# withAnalog.net
KiCad netlist of a schematic drawn in EAGLE
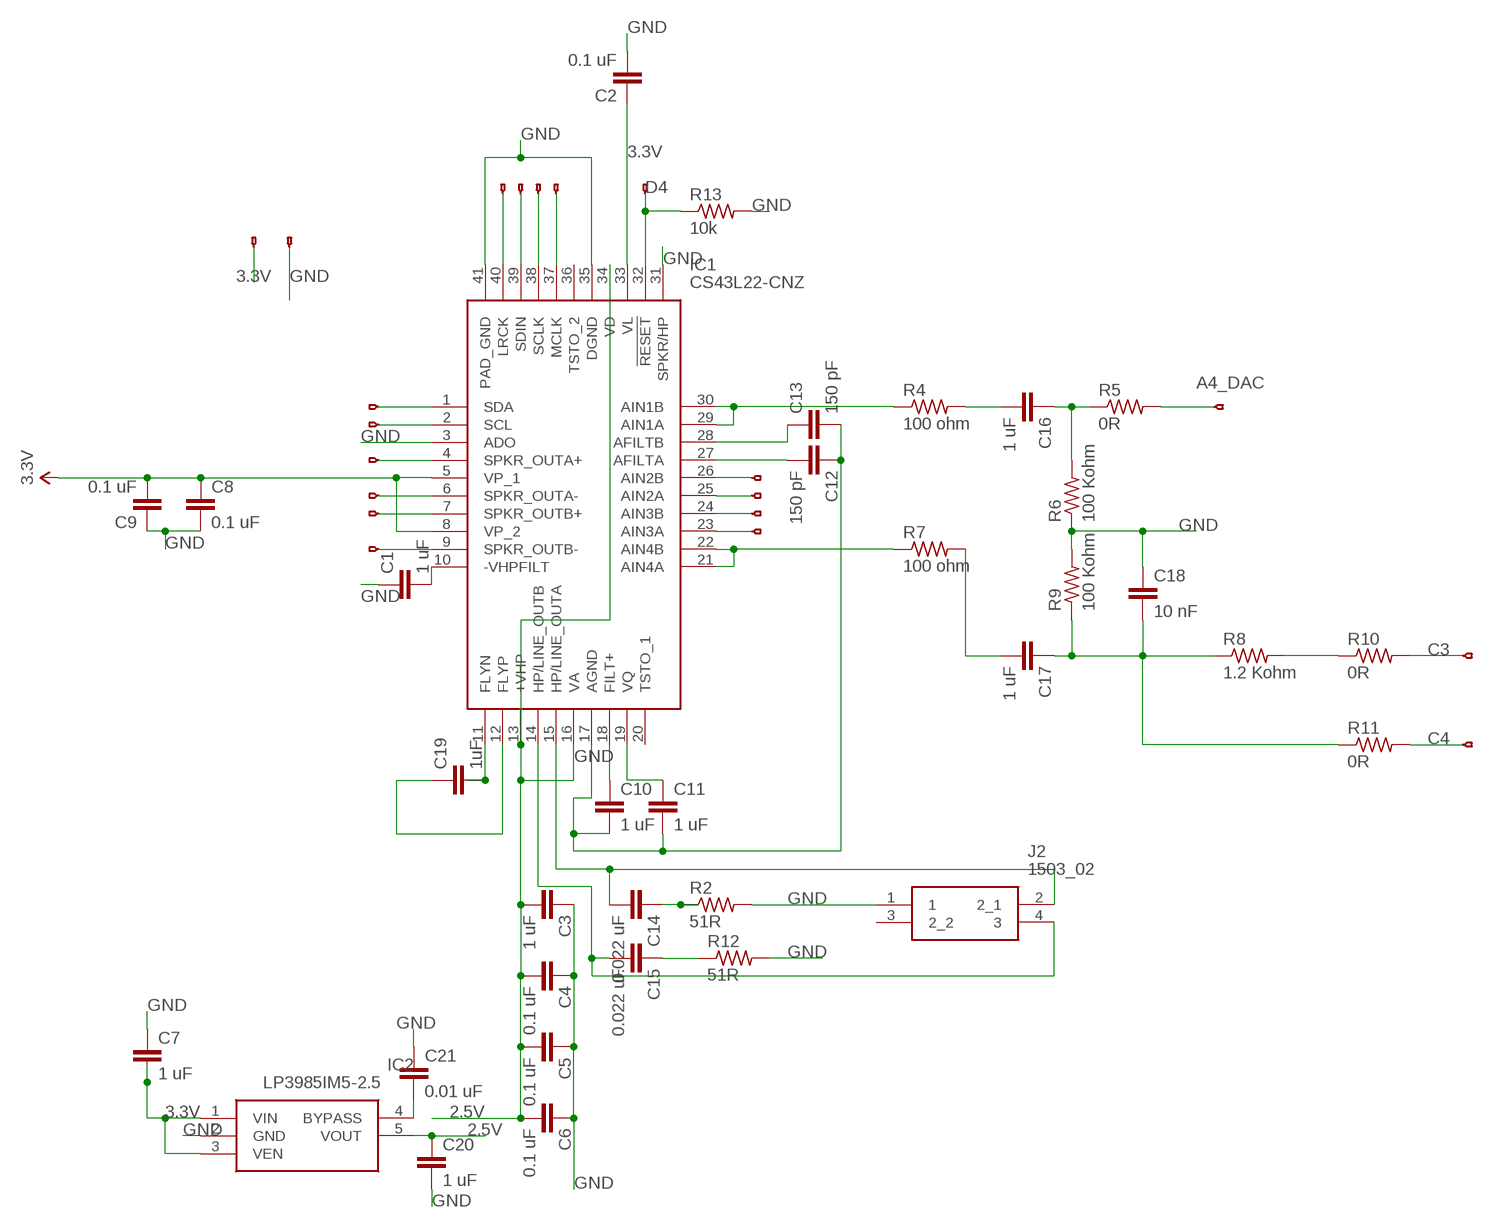
[diagram p0: schematic, sheet 1]

(export (version "E")
  (design (tool "Eeschema 10.0.6"))
  (components
    (comp (ref "C1")
      (value "1 uF")
      (footprint "eagle-import:CAP-PTH-SMALL-KIT")
      (libsource (lib "eagle-import") (part "CAPKIT"))
    )
    (comp (ref "C2")
      (value "0.1 uF")
      (footprint "eagle-import:CAP-PTH-SMALL-KIT")
      (libsource (lib "eagle-import") (part "CAPKIT"))
    )
    (comp (ref "C3")
      (value "1 uF")
      (footprint "eagle-import:CAP-PTH-SMALL-KIT")
      (libsource (lib "eagle-import") (part "CAPKIT"))
    )
    (comp (ref "C4")
      (value "0.1 uF")
      (footprint "eagle-import:CAP-PTH-SMALL-KIT")
      (libsource (lib "eagle-import") (part "CAPKIT"))
    )
    (comp (ref "C5")
      (value "0.1 uF")
      (footprint "eagle-import:CAP-PTH-SMALL-KIT")
      (libsource (lib "eagle-import") (part "CAPKIT"))
    )
    (comp (ref "C6")
      (value "0.1 uF")
      (footprint "eagle-import:CAP-PTH-SMALL-KIT")
      (libsource (lib "eagle-import") (part "CAPKIT"))
    )
    (comp (ref "C7")
      (value "1 uF")
      (footprint "eagle-import:CAP-PTH-SMALL-KIT")
      (libsource (lib "eagle-import") (part "CAPKIT"))
    )
    (comp (ref "C8")
      (value "0.1 uF")
      (footprint "eagle-import:CAP-PTH-SMALL-KIT")
      (libsource (lib "eagle-import") (part "CAPKIT"))
    )
    (comp (ref "C9")
      (value "0.1 uF")
      (footprint "eagle-import:CAP-PTH-SMALL-KIT")
      (libsource (lib "eagle-import") (part "CAPKIT"))
    )
    (comp (ref "C10")
      (value "1 uF")
      (footprint "eagle-import:CAP-PTH-SMALL-KIT")
      (libsource (lib "eagle-import") (part "CAPKIT"))
    )
    (comp (ref "C11")
      (value "1 uF")
      (footprint "eagle-import:CAP-PTH-SMALL-KIT")
      (libsource (lib "eagle-import") (part "CAPKIT"))
    )
    (comp (ref "C12")
      (value "150 pF")
      (footprint "eagle-import:CAP-PTH-SMALL-KIT")
      (libsource (lib "eagle-import") (part "CAPKIT"))
    )
    (comp (ref "C13")
      (value "150 pF")
      (footprint "eagle-import:CAP-PTH-SMALL-KIT")
      (libsource (lib "eagle-import") (part "CAPKIT"))
    )
    (comp (ref "C14")
      (value "0.022 uF")
      (footprint "eagle-import:CAP-PTH-SMALL-KIT")
      (libsource (lib "eagle-import") (part "CAPKIT"))
    )
    (comp (ref "C15")
      (value "0.022 uF")
      (footprint "eagle-import:CAP-PTH-SMALL-KIT")
      (libsource (lib "eagle-import") (part "CAPKIT"))
    )
    (comp (ref "C16")
      (value "1 uF")
      (footprint "eagle-import:CAP-PTH-SMALL-KIT")
      (libsource (lib "eagle-import") (part "CAPKIT"))
    )
    (comp (ref "C17")
      (value "1 uF")
      (footprint "eagle-import:CAP-PTH-SMALL-KIT")
      (libsource (lib "eagle-import") (part "CAPKIT"))
    )
    (comp (ref "C18")
      (value "10 nF")
      (footprint "eagle-import:CAP-PTH-SMALL-KIT")
      (libsource (lib "eagle-import") (part "CAPKIT"))
    )
    (comp (ref "C19")
      (value "1uF")
      (footprint "eagle-import:C2.5-3")
      (libsource (lib "eagle-import") (part "C2,5-3"))
    )
    (comp (ref "C20")
      (value "1 uF")
      (footprint "eagle-import:CAP-PTH-SMALL-KIT")
      (libsource (lib "eagle-import") (part "CAPKIT"))
    )
    (comp (ref "C21")
      (value "0.01 uF")
      (footprint "eagle-import:CAP-PTH-SMALL-KIT")
      (libsource (lib "eagle-import") (part "CAPKIT"))
    )
    (comp (ref "IC1")
      (value "CS43L22-CNZ")
      (footprint "eagle-import:QFN50P600X600X100-41N")
      (fields
        (field (name "MOUSER_PART_NUMBER") "777-CS43L22-CNZ")
        (field (name "RS_PART_NUMBER") "7165851P")
      )
      (libsource (lib "eagle-import") (part "CS43L22-CNZ"))
    )
    (comp (ref "IC2")
      (value "LP3985IM5-2.5")
      (footprint "eagle-import:SOT95P300X120-5N")
      (fields
        (field (name "MOUSER_PART_NUMBER") "926-LP3985IM5-25")
        (field (name "RS_PART_NUMBER") "4433167")
      )
      (libsource (lib "eagle-import") (part "LP3985IM5-2.5"))
    )
    (comp (ref "J2")
      (value "1503_02")
      (footprint "eagle-import:150302")
      (fields (field (name "MANUFACTURER_PART_NUMBER") "1503 02"))
      (libsource (lib "eagle-import") (part "1503_02"))
    )
    (comp (ref "JP1")
      (value "HEADERHOLE-HEADERHOLE")
      (footprint "eagle-import:1X1-HEADER-HOLE")
      (libsource (lib "eagle-import") (part "HEADERHOLE-HEADERHOLE"))
    )
    (comp (ref "JP2")
      (value "HEADERHOLE-HEADERHOLE")
      (footprint "eagle-import:1X1-HEADER-HOLE")
      (libsource (lib "eagle-import") (part "HEADERHOLE-HEADERHOLE"))
    )
    (comp (ref "JP3")
      (value "HEADERHOLE-HEADERHOLE")
      (footprint "eagle-import:1X1-HEADER-HOLE")
      (libsource (lib "eagle-import") (part "HEADERHOLE-HEADERHOLE"))
    )
    (comp (ref "JP4")
      (value "HEADERHOLE-HEADERHOLE")
      (footprint "eagle-import:1X1-HEADER-HOLE")
      (libsource (lib "eagle-import") (part "HEADERHOLE-HEADERHOLE"))
    )
    (comp (ref "JP5")
      (value "HEADERHOLE-HEADERHOLE")
      (footprint "eagle-import:1X1-HEADER-HOLE")
      (libsource (lib "eagle-import") (part "HEADERHOLE-HEADERHOLE"))
    )
    (comp (ref "JP6")
      (value "HEADERHOLE-HEADERHOLE")
      (footprint "eagle-import:1X1-HEADER-HOLE")
      (libsource (lib "eagle-import") (part "HEADERHOLE-HEADERHOLE"))
    )
    (comp (ref "JP7")
      (value "HEADERHOLE-HEADERHOLE")
      (footprint "eagle-import:1X1-HEADER-HOLE")
      (libsource (lib "eagle-import") (part "HEADERHOLE-HEADERHOLE"))
    )
    (comp (ref "JP8")
      (value "HEADERHOLE-HEADERHOLE")
      (footprint "eagle-import:1X1-HEADER-HOLE")
      (libsource (lib "eagle-import") (part "HEADERHOLE-HEADERHOLE"))
    )
    (comp (ref "JP9")
      (value "HEADERHOLE-HEADERHOLE")
      (footprint "eagle-import:1X1-HEADER-HOLE")
      (libsource (lib "eagle-import") (part "HEADERHOLE-HEADERHOLE"))
    )
    (comp (ref "JP10")
      (value "HEADERHOLE-HEADERHOLE")
      (footprint "eagle-import:1X1-HEADER-HOLE")
      (libsource (lib "eagle-import") (part "HEADERHOLE-HEADERHOLE"))
    )
    (comp (ref "JP11")
      (value "HEADERHOLE-HEADERHOLE")
      (footprint "eagle-import:1X1-HEADER-HOLE")
      (libsource (lib "eagle-import") (part "HEADERHOLE-HEADERHOLE"))
    )
    (comp (ref "JP12")
      (value "HEADERHOLE-HEADERHOLE")
      (footprint "eagle-import:1X1-HEADER-HOLE")
      (libsource (lib "eagle-import") (part "HEADERHOLE-HEADERHOLE"))
    )
    (comp (ref "JP13")
      (value "HEADERHOLE-HEADERHOLE")
      (footprint "eagle-import:1X1-HEADER-HOLE")
      (libsource (lib "eagle-import") (part "HEADERHOLE-HEADERHOLE"))
    )
    (comp (ref "JP14")
      (value "HEADERHOLE-HEADERHOLE")
      (footprint "eagle-import:1X1-HEADER-HOLE")
      (libsource (lib "eagle-import") (part "HEADERHOLE-HEADERHOLE"))
    )
    (comp (ref "JP15")
      (value "HEADERHOLE-HEADERHOLE")
      (footprint "eagle-import:1X1-HEADER-HOLE")
      (libsource (lib "eagle-import") (part "HEADERHOLE-HEADERHOLE"))
    )
    (comp (ref "JP16")
      (value "HEADERHOLE-HEADERHOLE")
      (footprint "eagle-import:1X1-HEADER-HOLE")
      (libsource (lib "eagle-import") (part "HEADERHOLE-HEADERHOLE"))
    )
    (comp (ref "JP17")
      (value "HEADERHOLE-HEADERHOLE")
      (footprint "eagle-import:1X1-HEADER-HOLE")
      (libsource (lib "eagle-import") (part "HEADERHOLE-HEADERHOLE"))
    )
    (comp (ref "JP20")
      (value "HEADERHOLE-HEADERHOLE")
      (footprint "eagle-import:1X1-HEADER-HOLE")
      (libsource (lib "eagle-import") (part "HEADERHOLE-HEADERHOLE"))
    )
    (comp (ref "JP21")
      (value "HEADERHOLE-HEADERHOLE")
      (footprint "eagle-import:1X1-HEADER-HOLE")
      (libsource (lib "eagle-import") (part "HEADERHOLE-HEADERHOLE"))
    )
    (comp (ref "JP22")
      (value "HEADERHOLE-HEADERHOLE")
      (footprint "eagle-import:1X1-HEADER-HOLE")
      (libsource (lib "eagle-import") (part "HEADERHOLE-HEADERHOLE"))
    )
    (comp (ref "R2")
      (value "51R")
      (footprint "eagle-import:0204V")
      (libsource (lib "eagle-import") (part "R-US_0204/2V"))
    )
    (comp (ref "R4")
      (value "100 ohm")
      (footprint "eagle-import:0204V")
      (libsource (lib "eagle-import") (part "R-US_0204/2V"))
    )
    (comp (ref "R5")
      (value "0R")
      (footprint "eagle-import:0204V")
      (libsource (lib "eagle-import") (part "R-US_0204/2V"))
    )
    (comp (ref "R6")
      (value "100 Kohm")
      (footprint "eagle-import:0204V")
      (libsource (lib "eagle-import") (part "R-US_0204/2V"))
    )
    (comp (ref "R7")
      (value "100 ohm")
      (footprint "eagle-import:0204V")
      (libsource (lib "eagle-import") (part "R-US_0204/2V"))
    )
    (comp (ref "R8")
      (value "1.2 Kohm")
      (footprint "eagle-import:0204V")
      (libsource (lib "eagle-import") (part "R-US_0204/2V"))
    )
    (comp (ref "R9")
      (value "100 Kohm")
      (footprint "eagle-import:0204V")
      (libsource (lib "eagle-import") (part "R-US_0204/2V"))
    )
    (comp (ref "R10")
      (value "0R")
      (footprint "eagle-import:0204V")
      (libsource (lib "eagle-import") (part "R-US_0204/2V"))
    )
    (comp (ref "R11")
      (value "0R")
      (footprint "eagle-import:0204V")
      (libsource (lib "eagle-import") (part "R-US_0204/2V"))
    )
    (comp (ref "R12")
      (value "51R")
      (footprint "eagle-import:0204V")
      (libsource (lib "eagle-import") (part "R-US_0204/2V"))
    )
    (comp (ref "R13")
      (value "10k")
      (footprint "eagle-import:0204V")
      (libsource (lib "eagle-import") (part "R-US_0204/2V"))
    )
  )
  (nets
    (net (code "1") (name "/2.5V") (class "Default")
      (node (ref "C20") (pin "1") (pinfunction "1_1") (pintype "passive"))
      (node (ref "C3") (pin "2") (pinfunction "2_2") (pintype "passive"))
      (node (ref "C4") (pin "2") (pinfunction "2_2") (pintype "passive"))
      (node (ref "C5") (pin "2") (pinfunction "2_2") (pintype "passive"))
      (node (ref "C6") (pin "2") (pinfunction "2_2") (pintype "passive"))
      (node (ref "IC1") (pin "13") (pinfunction "+VHP_13") (pintype "bidirectional"))
      (node (ref "IC1") (pin "16") (pinfunction "VA_16") (pintype "bidirectional"))
      (node (ref "IC1") (pin "34") (pinfunction "VD_34") (pintype "bidirectional"))
      (node (ref "IC2") (pin "5") (pinfunction "VOUT_5") (pintype "bidirectional"))
    )
    (net (code "2") (name "/A4_DAC") (class "Default")
      (node (ref "JP20") (pin "1") (pinfunction "P$1_1") (pintype "bidirectional"))
      (node (ref "R5") (pin "2") (pinfunction "2_2") (pintype "passive"))
    )
    (net (code "3") (name "/C3") (class "Default")
      (node (ref "JP21") (pin "1") (pinfunction "P$1_1") (pintype "bidirectional"))
      (node (ref "R10") (pin "2") (pinfunction "2_2") (pintype "passive"))
    )
    (net (code "4") (name "/C4") (class "Default")
      (node (ref "JP22") (pin "1") (pinfunction "P$1_1") (pintype "bidirectional"))
      (node (ref "R11") (pin "2") (pinfunction "2_2") (pintype "passive"))
    )
    (net (code "5") (name "/D4") (class "Default")
      (node (ref "IC1") (pin "32") (pinfunction "~{RESET}_32") (pintype "bidirectional"))
      (node (ref "JP7") (pin "1") (pinfunction "P$1_1") (pintype "bidirectional"))
      (node (ref "R13") (pin "1") (pinfunction "1_1") (pintype "passive"))
    )
    (net (code "6") (name "/GND") (class "Default")
      (node (ref "C1") (pin "1") (pinfunction "1_1") (pintype "passive"))
      (node (ref "C10") (pin "2") (pinfunction "2_2") (pintype "passive"))
      (node (ref "C11") (pin "2") (pinfunction "2_2") (pintype "passive"))
      (node (ref "C12") (pin "1") (pinfunction "1_1") (pintype "passive"))
      (node (ref "C13") (pin "2") (pinfunction "2_2") (pintype "passive"))
      (node (ref "C18") (pin "1") (pinfunction "1_1") (pintype "passive"))
      (node (ref "C2") (pin "2") (pinfunction "2_2") (pintype "passive"))
      (node (ref "C20") (pin "2") (pinfunction "2_2") (pintype "passive"))
      (node (ref "C21") (pin "1") (pinfunction "1_1") (pintype "passive"))
      (node (ref "C3") (pin "1") (pinfunction "1_1") (pintype "passive"))
      (node (ref "C4") (pin "1") (pinfunction "1_1") (pintype "passive"))
      (node (ref "C5") (pin "1") (pinfunction "1_1") (pintype "passive"))
      (node (ref "C6") (pin "1") (pinfunction "1_1") (pintype "passive"))
      (node (ref "C7") (pin "1") (pinfunction "1_1") (pintype "passive"))
      (node (ref "C8") (pin "2") (pinfunction "2_2") (pintype "passive"))
      (node (ref "C9") (pin "1") (pinfunction "1_1") (pintype "passive"))
      (node (ref "IC1") (pin "17") (pinfunction "AGND_17") (pintype "bidirectional"))
      (node (ref "IC1") (pin "3") (pinfunction "ADO_3") (pintype "bidirectional"))
      (node (ref "IC1") (pin "31") (pinfunction "SPKR/HP_31") (pintype "bidirectional"))
      (node (ref "IC1") (pin "35") (pinfunction "DGND_35") (pintype "bidirectional"))
      (node (ref "IC1") (pin "41") (pinfunction "PAD_GND_41") (pintype "bidirectional"))
      (node (ref "IC2") (pin "2") (pinfunction "GND_2") (pintype "bidirectional"))
      (node (ref "J2") (pin "1") (pinfunction "1_1") (pintype "bidirectional"))
      (node (ref "JP9") (pin "1") (pinfunction "P$1_1") (pintype "bidirectional"))
      (node (ref "R12") (pin "2") (pinfunction "2_2") (pintype "passive"))
      (node (ref "R13") (pin "2") (pinfunction "2_2") (pintype "passive"))
      (node (ref "R2") (pin "2") (pinfunction "2_2") (pintype "passive"))
      (node (ref "R6") (pin "1") (pinfunction "1_1") (pintype "passive"))
      (node (ref "R9") (pin "2") (pinfunction "2_2") (pintype "passive"))
    )
    (net (code "7") (name "3.3V") (class "Default")
      (node (ref "C2") (pin "1") (pinfunction "1_1") (pintype "passive"))
      (node (ref "C7") (pin "2") (pinfunction "2_2") (pintype "passive"))
      (node (ref "C8") (pin "1") (pinfunction "1_1") (pintype "passive"))
      (node (ref "C9") (pin "2") (pinfunction "2_2") (pintype "passive"))
      (node (ref "IC1") (pin "33") (pinfunction "VL_33") (pintype "bidirectional"))
      (node (ref "IC1") (pin "5") (pinfunction "VP_1_5") (pintype "bidirectional"))
      (node (ref "IC1") (pin "8") (pinfunction "VP_2_8") (pintype "bidirectional"))
      (node (ref "IC2") (pin "1") (pinfunction "VIN_1") (pintype "bidirectional"))
      (node (ref "IC2") (pin "3") (pinfunction "VEN_3") (pintype "bidirectional"))
      (node (ref "JP8") (pin "1") (pinfunction "P$1_1") (pintype "bidirectional"))
    )
    (net (code "8") (name "Net-(C14-Pad1)") (class "Default")
      (node (ref "C14") (pin "1") (pinfunction "1_1") (pintype "passive"))
      (node (ref "R2") (pin "1") (pinfunction "1_1") (pintype "passive"))
    )
    (net (code "9") (name "Net-(C15-Pad1)") (class "Default")
      (node (ref "C15") (pin "1") (pinfunction "1_1") (pintype "passive"))
      (node (ref "R12") (pin "1") (pinfunction "1_1") (pintype "passive"))
    )
    (net (code "10") (name "Net-(C16-Pad1)") (class "Default")
      (node (ref "C16") (pin "1") (pinfunction "1_1") (pintype "passive"))
      (node (ref "R5") (pin "1") (pinfunction "1_1") (pintype "passive"))
      (node (ref "R6") (pin "2") (pinfunction "2_2") (pintype "passive"))
    )
    (net (code "11") (name "Net-(C16-Pad2)") (class "Default")
      (node (ref "C16") (pin "2") (pinfunction "2_2") (pintype "passive"))
      (node (ref "R4") (pin "2") (pinfunction "2_2") (pintype "passive"))
    )
    (net (code "12") (name "Net-(C17-Pad1)") (class "Default")
      (node (ref "C17") (pin "1") (pinfunction "1_1") (pintype "passive"))
      (node (ref "C18") (pin "2") (pinfunction "2_2") (pintype "passive"))
      (node (ref "R11") (pin "1") (pinfunction "1_1") (pintype "passive"))
      (node (ref "R8") (pin "1") (pinfunction "1_1") (pintype "passive"))
      (node (ref "R9") (pin "1") (pinfunction "1_1") (pintype "passive"))
    )
    (net (code "13") (name "Net-(C17-Pad2)") (class "Default")
      (node (ref "C17") (pin "2") (pinfunction "2_2") (pintype "passive"))
      (node (ref "R7") (pin "2") (pinfunction "2_2") (pintype "passive"))
    )
    (net (code "14") (name "Net-(IC1--VHPFILT)") (class "Default")
      (node (ref "C1") (pin "2") (pinfunction "2_2") (pintype "passive"))
      (node (ref "IC1") (pin "10") (pinfunction "-VHPFILT_10") (pintype "bidirectional"))
    )
    (net (code "15") (name "Net-(IC1-AFILTA)") (class "Default")
      (node (ref "C12") (pin "2") (pinfunction "2_2") (pintype "passive"))
      (node (ref "IC1") (pin "27") (pinfunction "AFILTA_27") (pintype "bidirectional"))
    )
    (net (code "16") (name "Net-(IC1-AFILTB)") (class "Default")
      (node (ref "C13") (pin "1") (pinfunction "1_1") (pintype "passive"))
      (node (ref "IC1") (pin "28") (pinfunction "AFILTB_28") (pintype "bidirectional"))
    )
    (net (code "17") (name "Net-(IC1-AIN1A)") (class "Default")
      (node (ref "IC1") (pin "29") (pinfunction "AIN1A_29") (pintype "bidirectional"))
      (node (ref "IC1") (pin "30") (pinfunction "AIN1B_30") (pintype "bidirectional"))
      (node (ref "R4") (pin "1") (pinfunction "1_1") (pintype "passive"))
    )
    (net (code "18") (name "Net-(IC1-AIN2A)") (class "Default")
      (node (ref "IC1") (pin "25") (pinfunction "AIN2A_25") (pintype "bidirectional"))
      (node (ref "JP16") (pin "1") (pinfunction "P$1_1") (pintype "bidirectional"))
    )
    (net (code "19") (name "Net-(IC1-AIN2B)") (class "Default")
      (node (ref "IC1") (pin "26") (pinfunction "AIN2B_26") (pintype "bidirectional"))
      (node (ref "JP17") (pin "1") (pinfunction "P$1_1") (pintype "bidirectional"))
    )
    (net (code "20") (name "Net-(IC1-AIN3A)") (class "Default")
      (node (ref "IC1") (pin "23") (pinfunction "AIN3A_23") (pintype "bidirectional"))
      (node (ref "JP14") (pin "1") (pinfunction "P$1_1") (pintype "bidirectional"))
    )
    (net (code "21") (name "Net-(IC1-AIN3B)") (class "Default")
      (node (ref "IC1") (pin "24") (pinfunction "AIN3B_24") (pintype "bidirectional"))
      (node (ref "JP15") (pin "1") (pinfunction "P$1_1") (pintype "bidirectional"))
    )
    (net (code "22") (name "Net-(IC1-AIN4A)") (class "Default")
      (node (ref "IC1") (pin "21") (pinfunction "AIN4A_21") (pintype "bidirectional"))
      (node (ref "IC1") (pin "22") (pinfunction "AIN4B_22") (pintype "bidirectional"))
      (node (ref "R7") (pin "1") (pinfunction "1_1") (pintype "passive"))
    )
    (net (code "23") (name "Net-(IC1-FILT+)") (class "Default")
      (node (ref "C10") (pin "1") (pinfunction "1_1") (pintype "passive"))
      (node (ref "IC1") (pin "18") (pinfunction "FILT+_18") (pintype "bidirectional"))
    )
    (net (code "24") (name "Net-(IC1-FLYN)") (class "Default")
      (node (ref "C19") (pin "2") (pinfunction "2_2") (pintype "passive"))
      (node (ref "IC1") (pin "11") (pinfunction "FLYN_11") (pintype "bidirectional"))
    )
    (net (code "25") (name "Net-(IC1-FLYP)") (class "Default")
      (node (ref "C19") (pin "1") (pinfunction "1_1") (pintype "passive"))
      (node (ref "IC1") (pin "12") (pinfunction "FLYP_12") (pintype "bidirectional"))
    )
    (net (code "26") (name "Net-(IC1-HP{slash}LINE_OUTA)") (class "Default")
      (node (ref "C14") (pin "2") (pinfunction "2_2") (pintype "passive"))
      (node (ref "IC1") (pin "15") (pinfunction "HP/LINE_OUTA_15") (pintype "bidirectional"))
      (node (ref "J2") (pin "2") (pinfunction "2_1_2") (pintype "bidirectional"))
    )
    (net (code "27") (name "Net-(IC1-HP{slash}LINE_OUTB)") (class "Default")
      (node (ref "C15") (pin "2") (pinfunction "2_2") (pintype "passive"))
      (node (ref "IC1") (pin "14") (pinfunction "HP/LINE_OUTB_14") (pintype "bidirectional"))
      (node (ref "J2") (pin "4") (pinfunction "3_4") (pintype "bidirectional"))
    )
    (net (code "28") (name "Net-(IC1-LRCK)") (class "Default")
      (node (ref "IC1") (pin "40") (pinfunction "LRCK_40") (pintype "bidirectional"))
      (node (ref "JP6") (pin "1") (pinfunction "P$1_1") (pintype "bidirectional"))
    )
    (net (code "29") (name "Net-(IC1-MCLK)") (class "Default")
      (node (ref "IC1") (pin "37") (pinfunction "MCLK_37") (pintype "bidirectional"))
      (node (ref "JP3") (pin "1") (pinfunction "P$1_1") (pintype "bidirectional"))
    )
    (net (code "30") (name "Net-(IC1-SCL)") (class "Default")
      (node (ref "IC1") (pin "2") (pinfunction "SCL_2") (pintype "bidirectional"))
      (node (ref "JP2") (pin "1") (pinfunction "P$1_1") (pintype "bidirectional"))
    )
    (net (code "31") (name "Net-(IC1-SCLK)") (class "Default")
      (node (ref "IC1") (pin "38") (pinfunction "SCLK_38") (pintype "bidirectional"))
      (node (ref "JP4") (pin "1") (pinfunction "P$1_1") (pintype "bidirectional"))
    )
    (net (code "32") (name "Net-(IC1-SDA)") (class "Default")
      (node (ref "IC1") (pin "1") (pinfunction "SDA_1") (pintype "bidirectional"))
      (node (ref "JP1") (pin "1") (pinfunction "P$1_1") (pintype "bidirectional"))
    )
    (net (code "33") (name "Net-(IC1-SDIN)") (class "Default")
      (node (ref "IC1") (pin "39") (pinfunction "SDIN_39") (pintype "bidirectional"))
      (node (ref "JP5") (pin "1") (pinfunction "P$1_1") (pintype "bidirectional"))
    )
    (net (code "34") (name "Net-(IC1-SPKR_OUTA+)") (class "Default")
      (node (ref "IC1") (pin "4") (pinfunction "SPKR_OUTA+_4") (pintype "bidirectional"))
      (node (ref "JP10") (pin "1") (pinfunction "P$1_1") (pintype "bidirectional"))
    )
    (net (code "35") (name "Net-(IC1-SPKR_OUTA-)") (class "Default")
      (node (ref "IC1") (pin "6") (pinfunction "SPKR_OUTA-_6") (pintype "bidirectional"))
      (node (ref "JP11") (pin "1") (pinfunction "P$1_1") (pintype "bidirectional"))
    )
    (net (code "36") (name "Net-(IC1-SPKR_OUTB+)") (class "Default")
      (node (ref "IC1") (pin "7") (pinfunction "SPKR_OUTB+_7") (pintype "bidirectional"))
      (node (ref "JP12") (pin "1") (pinfunction "P$1_1") (pintype "bidirectional"))
    )
    (net (code "37") (name "Net-(IC1-SPKR_OUTB-)") (class "Default")
      (node (ref "IC1") (pin "9") (pinfunction "SPKR_OUTB-_9") (pintype "bidirectional"))
      (node (ref "JP13") (pin "1") (pinfunction "P$1_1") (pintype "bidirectional"))
    )
    (net (code "38") (name "Net-(IC1-VQ)") (class "Default")
      (node (ref "C11") (pin "1") (pinfunction "1_1") (pintype "passive"))
      (node (ref "IC1") (pin "19") (pinfunction "VQ_19") (pintype "bidirectional"))
    )
    (net (code "39") (name "Net-(IC2-BYPASS)") (class "Default")
      (node (ref "C21") (pin "2") (pinfunction "2_2") (pintype "passive"))
      (node (ref "IC2") (pin "4") (pinfunction "BYPASS_4") (pintype "bidirectional"))
    )
    (net (code "40") (name "Net-(R10-Pad1)") (class "Default")
      (node (ref "R10") (pin "1") (pinfunction "1_1") (pintype "passive"))
      (node (ref "R8") (pin "2") (pinfunction "2_2") (pintype "passive"))
    )
    (net (code "41") (name "unconnected-(IC1-TSTO_1-Pad20)") (class "Default")
      (node (ref "IC1") (pin "20") (pinfunction "TSTO_1_20") (pintype "bidirectional"))
    )
    (net (code "42") (name "unconnected-(IC1-TSTO_2-Pad36)") (class "Default")
      (node (ref "IC1") (pin "36") (pinfunction "TSTO_2_36") (pintype "bidirectional"))
    )
    (net (code "43") (name "unconnected-(J2-2_2-Pad3)") (class "Default")
      (node (ref "J2") (pin "3") (pinfunction "2_2_3") (pintype "bidirectional"))
    )
  )
)
